# design.net
KiCad netlist of a schematic drawn in Altium Designer
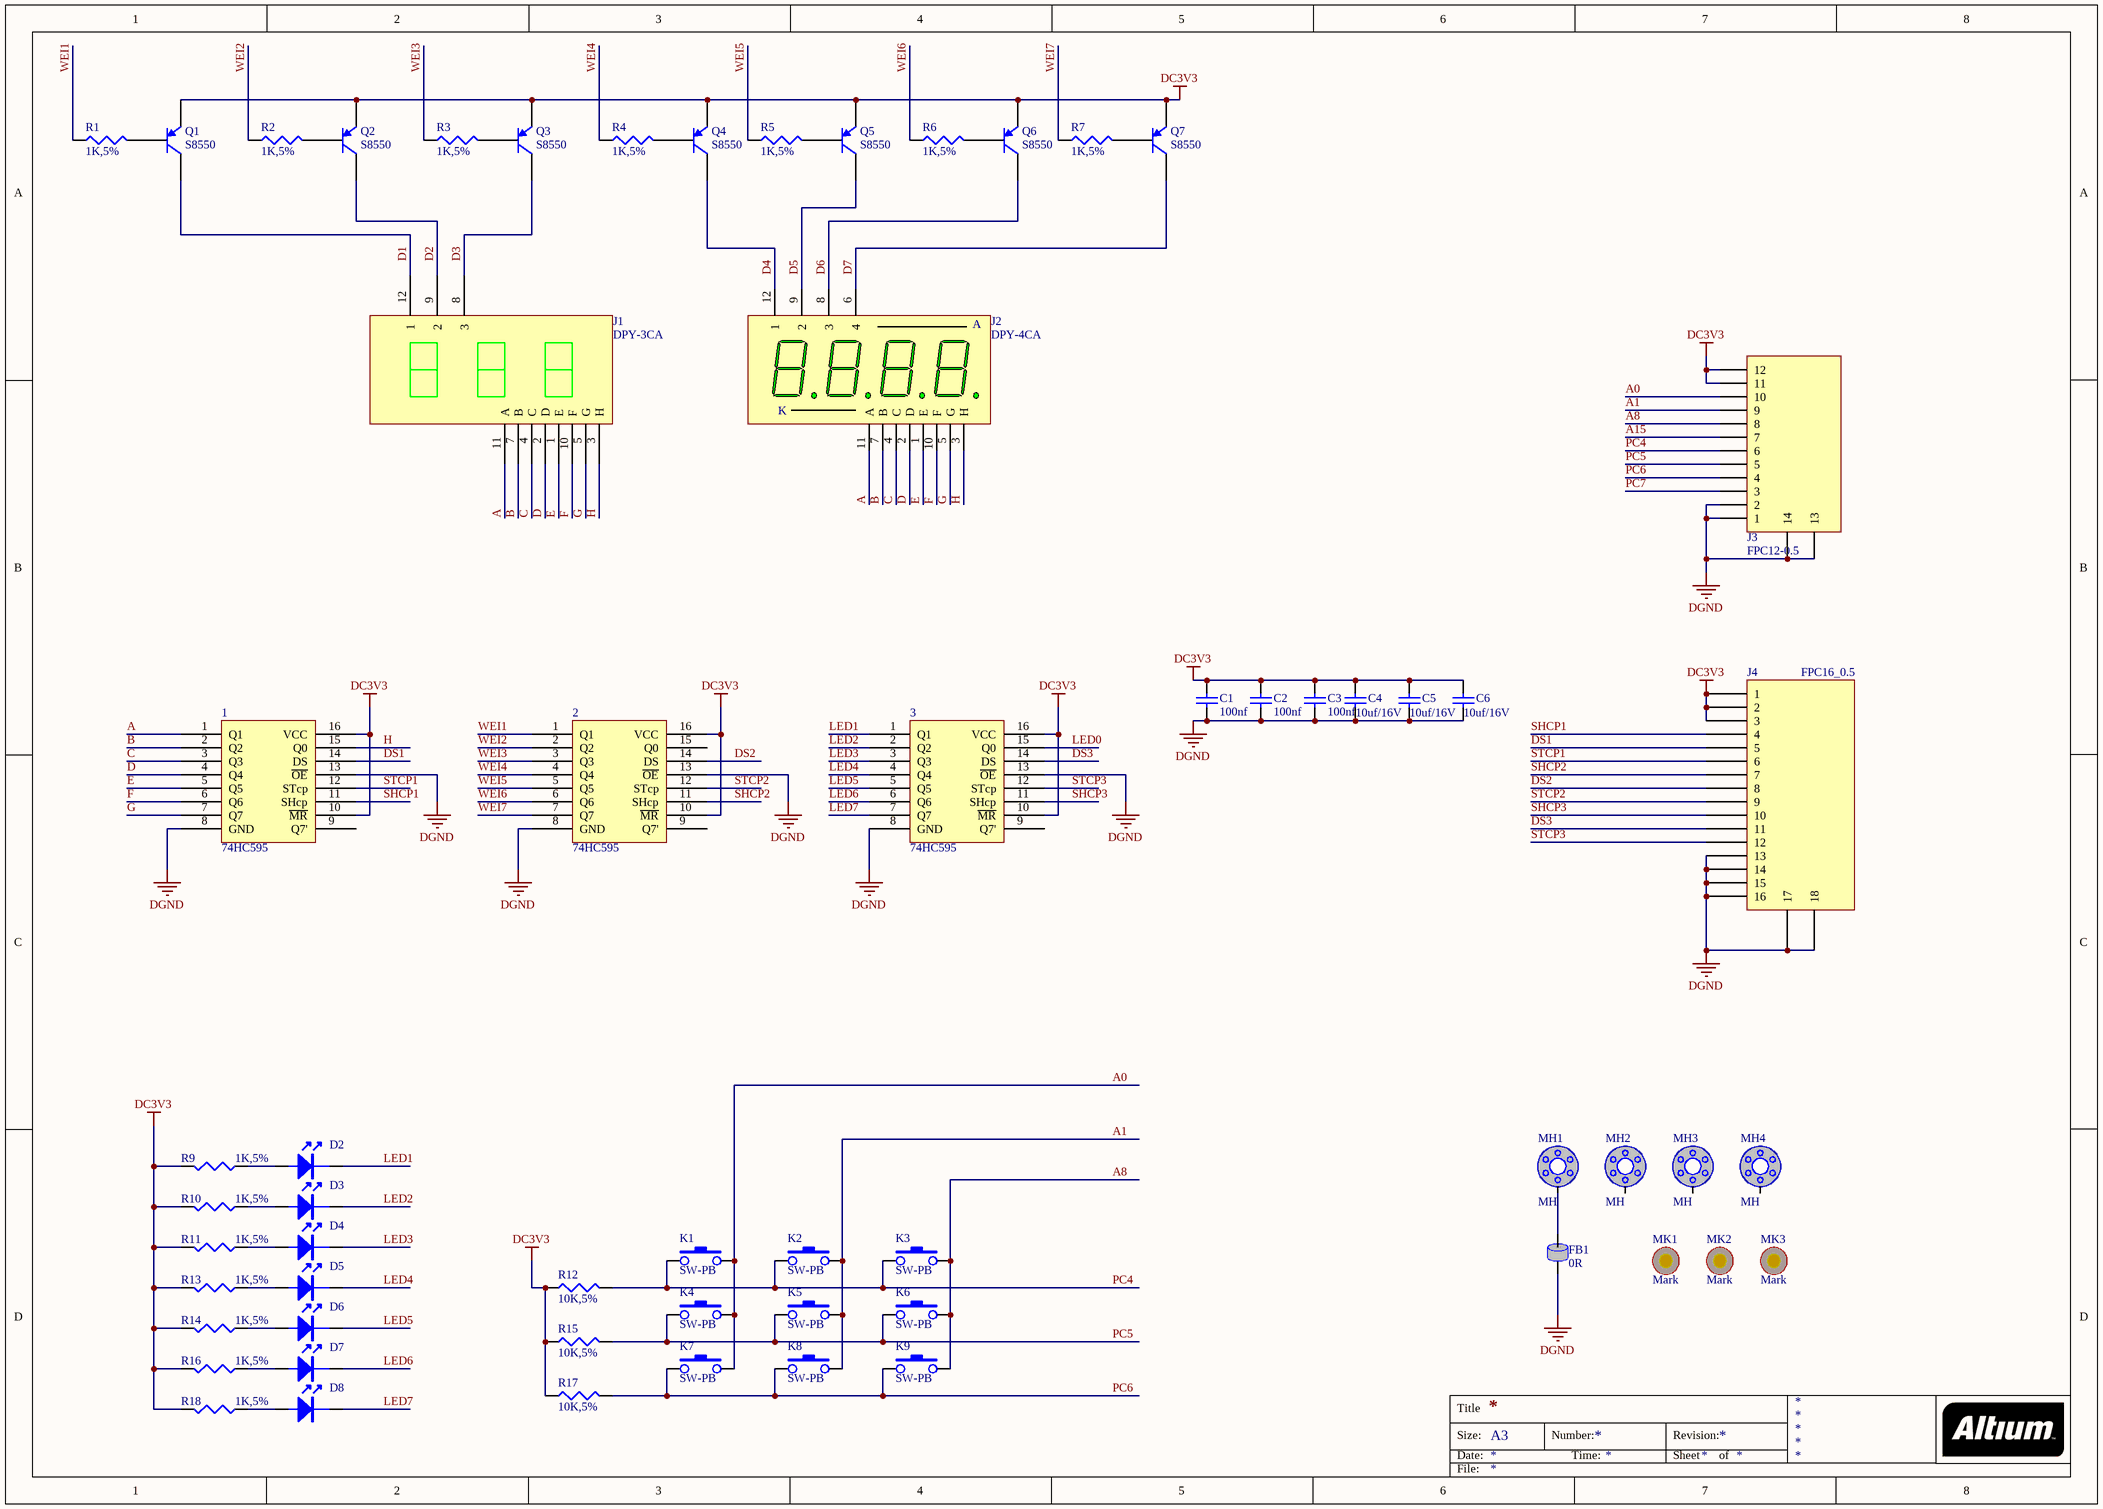
[diagram p0: 显示与输入.SchDoc]

(export (version "E")
  (design (tool "Eeschema 10.0.6"))
  (components
    (comp (ref "1") (value "74HC595") (footprint "SOIC-16") (libsource (lib "74HC595") (part "74HC595")))
    (comp (ref "2") (value "74HC595") (footprint "SOIC-16") (libsource (lib "74HC595") (part "74HC595")))
    (comp (ref "3") (value "74HC595") (footprint "SOIC-16") (libsource (lib "74HC595") (part "74HC595")))
    (comp (ref "C1")
      (value "100nf")
      (footprint "Cap0603")
      (description "无极性电容（表贴）")
      (libsource (lib "MyAD_Library") (part "Cap Semi"))
    )
    (comp (ref "C2")
      (value "100nf")
      (footprint "Cap0603")
      (description "无极性电容（表贴）")
      (libsource (lib "MyAD_Library") (part "Cap Semi"))
    )
    (comp (ref "C3")
      (value "100nf")
      (footprint "Cap0603")
      (description "无极性电容（表贴）")
      (libsource (lib "MyAD_Library") (part "Cap Semi"))
    )
    (comp (ref "C4")
      (value "10uf/16V")
      (footprint "Cap0603")
      (description "无极性电容（表贴）")
      (libsource (lib "MyAD_Library") (part "Cap Semi"))
    )
    (comp (ref "C5")
      (value "10uf/16V")
      (footprint "Cap0603")
      (description "无极性电容（表贴）")
      (libsource (lib "MyAD_Library") (part "Cap Semi"))
    )
    (comp (ref "C6")
      (value "10uf/16V")
      (footprint "Cap0603")
      (description "无极性电容（表贴）")
      (libsource (lib "MyAD_Library") (part "Cap Semi"))
    )
    (comp (ref "D2") (value "LED") (footprint "LED0603") (libsource (lib "MISCESCH") (part "LED")))
    (comp (ref "D3") (value "LED") (footprint "LED0603") (libsource (lib "MISCESCH") (part "LED")))
    (comp (ref "D4") (value "LED") (footprint "LED0603") (libsource (lib "MISCESCH") (part "LED")))
    (comp (ref "D5") (value "LED") (footprint "LED0603") (libsource (lib "MISCESCH") (part "LED")))
    (comp (ref "D6") (value "LED") (footprint "LED0603") (libsource (lib "MISCESCH") (part "LED")))
    (comp (ref "D7") (value "LED") (footprint "LED0603") (libsource (lib "MISCESCH") (part "LED")))
    (comp (ref "D8") (value "LED") (footprint "LED0603") (libsource (lib "MISCESCH") (part "LED")))
    (comp (ref "FB1")
      (value "0R")
      (footprint "FB0603")
      (description "磁珠")
      (libsource (lib "MyAD_Library") (part "FerriteBead"))
    )
    (comp (ref "J1")
      (value "DPY-3CA")
      (footprint "3位数码管0.56寸")
      (description "共阳3位数码管")
      (libsource (lib "fszhang") (part "DPY-3CA"))
    )
    (comp (ref "J2")
      (value "DPY-4CA")
      (footprint "4位数码管0.56寸")
      (description "共阳4位数码管")
      (libsource (lib "fszhang") (part "DPY-4CA"))
    )
    (comp (ref "J3")
      (value "FPC12-0.5")
      (footprint "FPC0.5-12P")
      (libsource (lib "MyAD_Library") (part "FPC12-0.5"))
    )
    (comp (ref "J4")
      (value "FPC16_0.5")
      (footprint "FPC0.5-16P")
      (libsource (lib "MyAD_Schlib") (part "FPC16_0.5"))
    )
    (comp (ref "K1") (value "SW-PB") (footprint "PCB-KEY") (libsource (lib "MISCESCH") (part "SW-PB")))
    (comp (ref "K2") (value "SW-PB") (footprint "PCB-KEY") (libsource (lib "MISCESCH") (part "SW-PB")))
    (comp (ref "K3") (value "SW-PB") (footprint "PCB-KEY") (libsource (lib "MISCESCH") (part "SW-PB")))
    (comp (ref "K4") (value "SW-PB") (footprint "PCB-KEY") (libsource (lib "MISCESCH") (part "SW-PB")))
    (comp (ref "K5") (value "SW-PB") (footprint "PCB-KEY") (libsource (lib "MISCESCH") (part "SW-PB")))
    (comp (ref "K6") (value "SW-PB") (footprint "PCB-KEY") (libsource (lib "MISCESCH") (part "SW-PB")))
    (comp (ref "K7") (value "SW-PB") (footprint "PCB-KEY") (libsource (lib "MISCESCH") (part "SW-PB")))
    (comp (ref "K8") (value "SW-PB") (footprint "PCB-KEY") (libsource (lib "MISCESCH") (part "SW-PB")))
    (comp (ref "K9") (value "SW-PB") (footprint "PCB-KEY") (libsource (lib "MISCESCH") (part "SW-PB")))
    (comp (ref "MH1")
      (value "MH")
      (footprint "AS_D3mm-6mm")
      (description "固定孔")
      (libsource (lib "MyAD_Library") (part "MH"))
    )
    (comp (ref "MH2")
      (value "MH")
      (footprint "AS_D3mm-6mm")
      (description "固定孔")
      (libsource (lib "MyAD_Library") (part "MH"))
    )
    (comp (ref "MH3")
      (value "MH")
      (footprint "AS_D3mm-6mm")
      (description "固定孔")
      (libsource (lib "MyAD_Library") (part "MH"))
    )
    (comp (ref "MH4")
      (value "MH")
      (footprint "AS_D3mm-6mm")
      (description "固定孔")
      (libsource (lib "MyAD_Library") (part "MH"))
    )
    (comp (ref "MK1")
      (value "Mark")
      (footprint "MK")
      (description "贴片马克点")
      (libsource (lib "MyAD_Library") (part "Mark"))
    )
    (comp (ref "MK2")
      (value "Mark")
      (footprint "MK")
      (description "贴片马克点")
      (libsource (lib "MyAD_Library") (part "Mark"))
    )
    (comp (ref "MK3")
      (value "Mark")
      (footprint "MK")
      (description "贴片马克点")
      (libsource (lib "MyAD_Library") (part "Mark"))
    )
    (comp (ref "Q1")
      (value "S8550")
      (footprint "SOT-23B")
      (description "PNP")
      (libsource (lib "MyAD_Schlib") (part "S8550"))
    )
    (comp (ref "Q2")
      (value "S8550")
      (footprint "SOT-23B")
      (description "PNP")
      (libsource (lib "MyAD_Schlib") (part "S8550"))
    )
    (comp (ref "Q3")
      (value "S8550")
      (footprint "SOT-23B")
      (description "PNP")
      (libsource (lib "MyAD_Schlib") (part "S8550"))
    )
    (comp (ref "Q4")
      (value "S8550")
      (footprint "SOT-23B")
      (description "PNP")
      (libsource (lib "MyAD_Schlib") (part "S8550"))
    )
    (comp (ref "Q5")
      (value "S8550")
      (footprint "SOT-23B")
      (description "PNP")
      (libsource (lib "MyAD_Schlib") (part "S8550"))
    )
    (comp (ref "Q6")
      (value "S8550")
      (footprint "SOT-23B")
      (description "PNP")
      (libsource (lib "MyAD_Schlib") (part "S8550"))
    )
    (comp (ref "Q7")
      (value "S8550")
      (footprint "SOT-23B")
      (description "PNP")
      (libsource (lib "MyAD_Schlib") (part "S8550"))
    )
    (comp (ref "R1")
      (value "1K,5%")
      (footprint "Res0603")
      (description "电阻")
      (libsource (lib "MyAD_Schlib") (part "Res"))
    )
    (comp (ref "R2")
      (value "1K,5%")
      (footprint "Res0603")
      (description "电阻")
      (libsource (lib "MyAD_Schlib") (part "Res"))
    )
    (comp (ref "R3")
      (value "1K,5%")
      (footprint "Res0603")
      (description "电阻")
      (libsource (lib "MyAD_Schlib") (part "Res"))
    )
    (comp (ref "R4")
      (value "1K,5%")
      (footprint "Res0603")
      (description "电阻")
      (libsource (lib "MyAD_Schlib") (part "Res"))
    )
    (comp (ref "R5")
      (value "1K,5%")
      (footprint "Res0603")
      (description "电阻")
      (libsource (lib "MyAD_Schlib") (part "Res"))
    )
    (comp (ref "R6")
      (value "1K,5%")
      (footprint "Res0603")
      (description "电阻")
      (libsource (lib "MyAD_Schlib") (part "Res"))
    )
    (comp (ref "R7")
      (value "1K,5%")
      (footprint "Res0603")
      (description "电阻")
      (libsource (lib "MyAD_Schlib") (part "Res"))
    )
    (comp (ref "R9")
      (value "1K,5%")
      (footprint "Res0603")
      (description "电阻")
      (libsource (lib "MyAD_Library") (part "Res"))
    )
    (comp (ref "R10")
      (value "1K,5%")
      (footprint "Res0603")
      (description "电阻")
      (libsource (lib "MyAD_Library") (part "Res"))
    )
    (comp (ref "R11")
      (value "1K,5%")
      (footprint "Res0603")
      (description "电阻")
      (libsource (lib "MyAD_Library") (part "Res"))
    )
    (comp (ref "R12")
      (value "10K,5%")
      (footprint "Res0603")
      (description "电阻")
      (libsource (lib "MyAD_Schlib") (part "Res"))
    )
    (comp (ref "R13")
      (value "1K,5%")
      (footprint "Res0603")
      (description "电阻")
      (libsource (lib "MyAD_Library") (part "Res"))
    )
    (comp (ref "R14")
      (value "1K,5%")
      (footprint "Res0603")
      (description "电阻")
      (libsource (lib "MyAD_Library") (part "Res"))
    )
    (comp (ref "R15")
      (value "10K,5%")
      (footprint "Res0603")
      (description "电阻")
      (libsource (lib "MyAD_Schlib") (part "Res"))
    )
    (comp (ref "R16")
      (value "1K,5%")
      (footprint "Res0603")
      (description "电阻")
      (libsource (lib "MyAD_Library") (part "Res"))
    )
    (comp (ref "R17")
      (value "10K,5%")
      (footprint "Res0603")
      (description "电阻")
      (libsource (lib "MyAD_Schlib") (part "Res"))
    )
    (comp (ref "R18")
      (value "1K,5%")
      (footprint "Res0603")
      (description "电阻")
      (libsource (lib "MyAD_Library") (part "Res"))
    )
  )
  (nets
    (net (code "1") (name "/A") (class "Default")
      (node (ref "1") (pin "1") (pinfunction "Q1_1") (pintype "passive"))
      (node (ref "J1") (pin "11") (pinfunction "A_11") (pintype "passive"))
      (node (ref "J2") (pin "11") (pinfunction "A_11") (pintype "passive"))
    )
    (net (code "2") (name "/A0") (class "Default")
      (node (ref "J3") (pin "10") (pinfunction "10_10") (pintype "passive"))
      (node (ref "K1") (pin "2") (pintype "passive"))
      (node (ref "K4") (pin "2") (pintype "passive"))
      (node (ref "K7") (pin "2") (pintype "passive"))
    )
    (net (code "3") (name "/A1") (class "Default")
      (node (ref "J3") (pin "9") (pinfunction "9_9") (pintype "passive"))
      (node (ref "K2") (pin "2") (pintype "passive"))
      (node (ref "K5") (pin "2") (pintype "passive"))
      (node (ref "K8") (pin "2") (pintype "passive"))
    )
    (net (code "4") (name "/A8") (class "Default")
      (node (ref "J3") (pin "8") (pinfunction "8_8") (pintype "passive"))
      (node (ref "K3") (pin "2") (pintype "passive"))
      (node (ref "K6") (pin "2") (pintype "passive"))
      (node (ref "K9") (pin "2") (pintype "passive"))
    )
    (net (code "5") (name "/A15") (class "Default")
      (node (ref "J3") (pin "7") (pinfunction "7_7") (pintype "passive"))
    )
    (net (code "6") (name "/B") (class "Default")
      (node (ref "1") (pin "2") (pinfunction "Q2_2") (pintype "passive"))
      (node (ref "J1") (pin "7") (pinfunction "B_7") (pintype "passive"))
      (node (ref "J2") (pin "7") (pinfunction "B_7") (pintype "passive"))
    )
    (net (code "7") (name "/C") (class "Default")
      (node (ref "1") (pin "3") (pinfunction "Q3_3") (pintype "passive"))
      (node (ref "J1") (pin "4") (pinfunction "C_4") (pintype "passive"))
      (node (ref "J2") (pin "4") (pinfunction "C_4") (pintype "passive"))
    )
    (net (code "8") (name "/D") (class "Default")
      (node (ref "1") (pin "4") (pinfunction "Q4_4") (pintype "passive"))
      (node (ref "J1") (pin "2") (pinfunction "D_2") (pintype "passive"))
      (node (ref "J2") (pin "2") (pinfunction "D_2") (pintype "passive"))
    )
    (net (code "9") (name "/D1") (class "Default")
      (node (ref "J1") (pin "12") (pinfunction "1_12") (pintype "passive"))
      (node (ref "Q1") (pin "2") (pinfunction "E_2") (pintype "passive"))
    )
    (net (code "10") (name "/D2") (class "Default")
      (node (ref "J1") (pin "9") (pinfunction "2_9") (pintype "passive"))
      (node (ref "Q2") (pin "2") (pinfunction "E_2") (pintype "passive"))
    )
    (net (code "11") (name "/D3") (class "Default")
      (node (ref "J1") (pin "8") (pinfunction "3_8") (pintype "passive"))
      (node (ref "Q3") (pin "2") (pinfunction "E_2") (pintype "passive"))
    )
    (net (code "12") (name "/D4") (class "Default")
      (node (ref "J2") (pin "12") (pinfunction "1_12") (pintype "passive"))
      (node (ref "Q4") (pin "2") (pinfunction "E_2") (pintype "passive"))
    )
    (net (code "13") (name "/D5") (class "Default")
      (node (ref "J2") (pin "9") (pinfunction "2_9") (pintype "passive"))
      (node (ref "Q5") (pin "2") (pinfunction "E_2") (pintype "passive"))
    )
    (net (code "14") (name "/D6") (class "Default")
      (node (ref "J2") (pin "8") (pinfunction "3_8") (pintype "passive"))
      (node (ref "Q6") (pin "2") (pinfunction "E_2") (pintype "passive"))
    )
    (net (code "15") (name "/D7") (class "Default")
      (node (ref "J2") (pin "6") (pinfunction "4_6") (pintype "passive"))
      (node (ref "Q7") (pin "2") (pinfunction "E_2") (pintype "passive"))
    )
    (net (code "16") (name "/DS1") (class "Default")
      (node (ref "1") (pin "14") (pinfunction "DS_14") (pintype "passive"))
      (node (ref "J4") (pin "5") (pinfunction "5_5") (pintype "passive"))
    )
    (net (code "17") (name "/DS2") (class "Default")
      (node (ref "2") (pin "14") (pinfunction "DS_14") (pintype "passive"))
      (node (ref "J4") (pin "8") (pinfunction "8_8") (pintype "passive"))
    )
    (net (code "18") (name "/DS3") (class "Default")
      (node (ref "3") (pin "14") (pinfunction "DS_14") (pintype "passive"))
      (node (ref "J4") (pin "11") (pinfunction "11_11") (pintype "passive"))
    )
    (net (code "19") (name "/E") (class "Default")
      (node (ref "1") (pin "5") (pinfunction "Q5_5") (pintype "passive"))
      (node (ref "J1") (pin "1") (pinfunction "E_1") (pintype "passive"))
      (node (ref "J2") (pin "1") (pinfunction "E_1") (pintype "passive"))
    )
    (net (code "20") (name "/F") (class "Default")
      (node (ref "1") (pin "6") (pinfunction "Q6_6") (pintype "passive"))
      (node (ref "J1") (pin "10") (pinfunction "F_10") (pintype "passive"))
      (node (ref "J2") (pin "10") (pinfunction "F_10") (pintype "passive"))
    )
    (net (code "21") (name "/G") (class "Default")
      (node (ref "1") (pin "7") (pinfunction "Q7_7") (pintype "passive"))
      (node (ref "J1") (pin "5") (pinfunction "G_5") (pintype "passive"))
      (node (ref "J2") (pin "5") (pinfunction "G_5") (pintype "passive"))
    )
    (net (code "22") (name "/H") (class "Default")
      (node (ref "1") (pin "15") (pinfunction "Q0_15") (pintype "passive"))
      (node (ref "J1") (pin "3") (pinfunction "H_3") (pintype "passive"))
      (node (ref "J2") (pin "3") (pinfunction "H_3") (pintype "passive"))
    )
    (net (code "23") (name "/LED0") (class "Default")
      (node (ref "3") (pin "15") (pinfunction "Q0_15") (pintype "passive"))
    )
    (net (code "24") (name "/LED1") (class "Default")
      (node (ref "3") (pin "1") (pinfunction "Q1_1") (pintype "passive"))
      (node (ref "D2") (pin "K") (pinfunction "2_K") (pintype "passive"))
    )
    (net (code "25") (name "/LED2") (class "Default")
      (node (ref "3") (pin "2") (pinfunction "Q2_2") (pintype "passive"))
      (node (ref "D3") (pin "K") (pinfunction "2_K") (pintype "passive"))
    )
    (net (code "26") (name "/LED3") (class "Default")
      (node (ref "3") (pin "3") (pinfunction "Q3_3") (pintype "passive"))
      (node (ref "D4") (pin "K") (pinfunction "2_K") (pintype "passive"))
    )
    (net (code "27") (name "/LED4") (class "Default")
      (node (ref "3") (pin "4") (pinfunction "Q4_4") (pintype "passive"))
      (node (ref "D5") (pin "K") (pinfunction "2_K") (pintype "passive"))
    )
    (net (code "28") (name "/LED5") (class "Default")
      (node (ref "3") (pin "5") (pinfunction "Q5_5") (pintype "passive"))
      (node (ref "D6") (pin "K") (pinfunction "2_K") (pintype "passive"))
    )
    (net (code "29") (name "/LED6") (class "Default")
      (node (ref "3") (pin "6") (pinfunction "Q6_6") (pintype "passive"))
      (node (ref "D7") (pin "K") (pinfunction "2_K") (pintype "passive"))
    )
    (net (code "30") (name "/LED7") (class "Default")
      (node (ref "3") (pin "7") (pinfunction "Q7_7") (pintype "passive"))
      (node (ref "D8") (pin "K") (pinfunction "2_K") (pintype "passive"))
    )
    (net (code "31") (name "/PC4") (class "Default")
      (node (ref "J3") (pin "6") (pinfunction "6_6") (pintype "passive"))
      (node (ref "K1") (pin "1") (pintype "passive"))
      (node (ref "K2") (pin "1") (pintype "passive"))
      (node (ref "K3") (pin "1") (pintype "passive"))
      (node (ref "R12") (pin "2") (pinfunction "2_2") (pintype "passive"))
    )
    (net (code "32") (name "/PC5") (class "Default")
      (node (ref "J3") (pin "5") (pinfunction "5_5") (pintype "passive"))
      (node (ref "K4") (pin "1") (pintype "passive"))
      (node (ref "K5") (pin "1") (pintype "passive"))
      (node (ref "K6") (pin "1") (pintype "passive"))
      (node (ref "R15") (pin "2") (pinfunction "2_2") (pintype "passive"))
    )
    (net (code "33") (name "/PC6") (class "Default")
      (node (ref "J3") (pin "4") (pinfunction "4_4") (pintype "passive"))
      (node (ref "K7") (pin "1") (pintype "passive"))
      (node (ref "K8") (pin "1") (pintype "passive"))
      (node (ref "K9") (pin "1") (pintype "passive"))
      (node (ref "R17") (pin "2") (pinfunction "2_2") (pintype "passive"))
    )
    (net (code "34") (name "/PC7") (class "Default")
      (node (ref "J3") (pin "3") (pinfunction "3_3") (pintype "passive"))
    )
    (net (code "35") (name "/SHCP1") (class "Default")
      (node (ref "1") (pin "11") (pinfunction "SHcp_11") (pintype "passive"))
      (node (ref "J4") (pin "4") (pinfunction "4_4") (pintype "passive"))
    )
    (net (code "36") (name "/SHCP2") (class "Default")
      (node (ref "2") (pin "11") (pinfunction "SHcp_11") (pintype "passive"))
      (node (ref "J4") (pin "7") (pinfunction "7_7") (pintype "passive"))
    )
    (net (code "37") (name "/SHCP3") (class "Default")
      (node (ref "3") (pin "11") (pinfunction "SHcp_11") (pintype "passive"))
      (node (ref "J4") (pin "10") (pinfunction "10_10") (pintype "passive"))
    )
    (net (code "38") (name "/STCP1") (class "Default")
      (node (ref "1") (pin "12") (pinfunction "STcp_12") (pintype "passive"))
      (node (ref "J4") (pin "6") (pinfunction "6_6") (pintype "passive"))
    )
    (net (code "39") (name "/STCP2") (class "Default")
      (node (ref "2") (pin "12") (pinfunction "STcp_12") (pintype "passive"))
      (node (ref "J4") (pin "9") (pinfunction "9_9") (pintype "passive"))
    )
    (net (code "40") (name "/STCP3") (class "Default")
      (node (ref "3") (pin "12") (pinfunction "STcp_12") (pintype "passive"))
      (node (ref "J4") (pin "12") (pinfunction "12_12") (pintype "passive"))
    )
    (net (code "41") (name "/WEI1") (class "Default")
      (node (ref "2") (pin "1") (pinfunction "Q1_1") (pintype "passive"))
      (node (ref "R1") (pin "1") (pinfunction "1_1") (pintype "passive"))
    )
    (net (code "42") (name "/WEI2") (class "Default")
      (node (ref "2") (pin "2") (pinfunction "Q2_2") (pintype "passive"))
      (node (ref "R2") (pin "1") (pinfunction "1_1") (pintype "passive"))
    )
    (net (code "43") (name "/WEI3") (class "Default")
      (node (ref "2") (pin "3") (pinfunction "Q3_3") (pintype "passive"))
      (node (ref "R3") (pin "1") (pinfunction "1_1") (pintype "passive"))
    )
    (net (code "44") (name "/WEI4") (class "Default")
      (node (ref "2") (pin "4") (pinfunction "Q4_4") (pintype "passive"))
      (node (ref "R4") (pin "1") (pinfunction "1_1") (pintype "passive"))
    )
    (net (code "45") (name "/WEI5") (class "Default")
      (node (ref "2") (pin "5") (pinfunction "Q5_5") (pintype "passive"))
      (node (ref "R5") (pin "1") (pinfunction "1_1") (pintype "passive"))
    )
    (net (code "46") (name "/WEI6") (class "Default")
      (node (ref "2") (pin "6") (pinfunction "Q6_6") (pintype "passive"))
      (node (ref "R6") (pin "1") (pinfunction "1_1") (pintype "passive"))
    )
    (net (code "47") (name "/WEI7") (class "Default")
      (node (ref "2") (pin "7") (pinfunction "Q7_7") (pintype "passive"))
      (node (ref "R7") (pin "1") (pinfunction "1_1") (pintype "passive"))
    )
    (net (code "48") (name "DC3V3") (class "Default")
      (node (ref "1") (pin "10") (pinfunction "~{MR}_10") (pintype "passive"))
      (node (ref "1") (pin "16") (pinfunction "VCC_16") (pintype "passive"))
      (node (ref "2") (pin "10") (pinfunction "~{MR}_10") (pintype "passive"))
      (node (ref "2") (pin "16") (pinfunction "VCC_16") (pintype "passive"))
      (node (ref "3") (pin "10") (pinfunction "~{MR}_10") (pintype "passive"))
      (node (ref "3") (pin "16") (pinfunction "VCC_16") (pintype "passive"))
      (node (ref "C1") (pin "2") (pinfunction "2_2") (pintype "passive"))
      (node (ref "C2") (pin "2") (pinfunction "2_2") (pintype "passive"))
      (node (ref "C3") (pin "2") (pinfunction "2_2") (pintype "passive"))
      (node (ref "C4") (pin "2") (pinfunction "2_2") (pintype "passive"))
      (node (ref "C5") (pin "2") (pinfunction "2_2") (pintype "passive"))
      (node (ref "C6") (pin "2") (pinfunction "2_2") (pintype "passive"))
      (node (ref "J3") (pin "11") (pinfunction "11_11") (pintype "passive"))
      (node (ref "J3") (pin "12") (pinfunction "12_12") (pintype "passive"))
      (node (ref "J4") (pin "1") (pinfunction "1_1") (pintype "passive"))
      (node (ref "J4") (pin "2") (pinfunction "2_2") (pintype "passive"))
      (node (ref "J4") (pin "3") (pinfunction "3_3") (pintype "passive"))
      (node (ref "Q1") (pin "3") (pinfunction "C_3") (pintype "passive"))
      (node (ref "Q2") (pin "3") (pinfunction "C_3") (pintype "passive"))
      (node (ref "Q3") (pin "3") (pinfunction "C_3") (pintype "passive"))
      (node (ref "Q4") (pin "3") (pinfunction "C_3") (pintype "passive"))
      (node (ref "Q5") (pin "3") (pinfunction "C_3") (pintype "passive"))
      (node (ref "Q6") (pin "3") (pinfunction "C_3") (pintype "passive"))
      (node (ref "Q7") (pin "3") (pinfunction "C_3") (pintype "passive"))
      (node (ref "R10") (pin "1") (pinfunction "1_1") (pintype "passive"))
      (node (ref "R11") (pin "1") (pinfunction "1_1") (pintype "passive"))
      (node (ref "R12") (pin "1") (pinfunction "1_1") (pintype "passive"))
      (node (ref "R13") (pin "1") (pinfunction "1_1") (pintype "passive"))
      (node (ref "R14") (pin "1") (pinfunction "1_1") (pintype "passive"))
      (node (ref "R15") (pin "1") (pinfunction "1_1") (pintype "passive"))
      (node (ref "R16") (pin "1") (pinfunction "1_1") (pintype "passive"))
      (node (ref "R17") (pin "1") (pinfunction "1_1") (pintype "passive"))
      (node (ref "R18") (pin "1") (pinfunction "1_1") (pintype "passive"))
      (node (ref "R9") (pin "1") (pinfunction "1_1") (pintype "passive"))
    )
    (net (code "49") (name "DGND") (class "Default")
      (node (ref "1") (pin "13") (pinfunction "~{OE}_13") (pintype "passive"))
      (node (ref "1") (pin "8") (pinfunction "GND_8") (pintype "passive"))
      (node (ref "2") (pin "13") (pinfunction "~{OE}_13") (pintype "passive"))
      (node (ref "2") (pin "8") (pinfunction "GND_8") (pintype "passive"))
      (node (ref "3") (pin "13") (pinfunction "~{OE}_13") (pintype "passive"))
      (node (ref "3") (pin "8") (pinfunction "GND_8") (pintype "passive"))
      (node (ref "C1") (pin "1") (pinfunction "1_1") (pintype "passive"))
      (node (ref "C2") (pin "1") (pinfunction "1_1") (pintype "passive"))
      (node (ref "C3") (pin "1") (pinfunction "1_1") (pintype "passive"))
      (node (ref "C4") (pin "1") (pinfunction "1_1") (pintype "passive"))
      (node (ref "C5") (pin "1") (pinfunction "1_1") (pintype "passive"))
      (node (ref "C6") (pin "1") (pinfunction "1_1") (pintype "passive"))
      (node (ref "FB1") (pin "1") (pinfunction "1_1") (pintype "passive"))
      (node (ref "J3") (pin "1") (pinfunction "1_1") (pintype "passive"))
      (node (ref "J3") (pin "13") (pinfunction "13_13") (pintype "passive"))
      (node (ref "J3") (pin "14") (pinfunction "14_14") (pintype "passive"))
      (node (ref "J3") (pin "2") (pinfunction "2_2") (pintype "passive"))
      (node (ref "J4") (pin "13") (pinfunction "13_13") (pintype "passive"))
      (node (ref "J4") (pin "14") (pinfunction "14_14") (pintype "passive"))
      (node (ref "J4") (pin "15") (pinfunction "15_15") (pintype "passive"))
      (node (ref "J4") (pin "16") (pinfunction "16_16") (pintype "passive"))
      (node (ref "J4") (pin "17") (pinfunction "17_17") (pintype "passive"))
      (node (ref "J4") (pin "18") (pinfunction "18_18") (pintype "passive"))
    )
    (net (code "50") (name "Net-(D2-1)") (class "Default")
      (node (ref "D2") (pin "A") (pinfunction "1_A") (pintype "passive"))
      (node (ref "R9") (pin "2") (pinfunction "2_2") (pintype "passive"))
    )
    (net (code "51") (name "Net-(D3-1)") (class "Default")
      (node (ref "D3") (pin "A") (pinfunction "1_A") (pintype "passive"))
      (node (ref "R10") (pin "2") (pinfunction "2_2") (pintype "passive"))
    )
    (net (code "52") (name "Net-(D4-1)") (class "Default")
      (node (ref "D4") (pin "A") (pinfunction "1_A") (pintype "passive"))
      (node (ref "R11") (pin "2") (pinfunction "2_2") (pintype "passive"))
    )
    (net (code "53") (name "Net-(D5-1)") (class "Default")
      (node (ref "D5") (pin "A") (pinfunction "1_A") (pintype "passive"))
      (node (ref "R13") (pin "2") (pinfunction "2_2") (pintype "passive"))
    )
    (net (code "54") (name "Net-(D6-1)") (class "Default")
      (node (ref "D6") (pin "A") (pinfunction "1_A") (pintype "passive"))
      (node (ref "R14") (pin "2") (pinfunction "2_2") (pintype "passive"))
    )
    (net (code "55") (name "Net-(D7-1)") (class "Default")
      (node (ref "D7") (pin "A") (pinfunction "1_A") (pintype "passive"))
      (node (ref "R16") (pin "2") (pinfunction "2_2") (pintype "passive"))
    )
    (net (code "56") (name "Net-(D8-1)") (class "Default")
      (node (ref "D8") (pin "A") (pinfunction "1_A") (pintype "passive"))
      (node (ref "R18") (pin "2") (pinfunction "2_2") (pintype "passive"))
    )
    (net (code "57") (name "Net-(FB1-Pad2)") (class "Default")
      (node (ref "FB1") (pin "2") (pinfunction "2_2") (pintype "passive"))
      (node (ref "MH1") (pin "MH1") (pinfunction "MH1_MH1") (pintype "passive"))
    )
    (net (code "58") (name "Net-(Q1-B)") (class "Default")
      (node (ref "Q1") (pin "1") (pinfunction "B_1") (pintype "passive"))
      (node (ref "R1") (pin "2") (pinfunction "2_2") (pintype "passive"))
    )
    (net (code "59") (name "Net-(Q2-B)") (class "Default")
      (node (ref "Q2") (pin "1") (pinfunction "B_1") (pintype "passive"))
      (node (ref "R2") (pin "2") (pinfunction "2_2") (pintype "passive"))
    )
    (net (code "60") (name "Net-(Q3-B)") (class "Default")
      (node (ref "Q3") (pin "1") (pinfunction "B_1") (pintype "passive"))
      (node (ref "R3") (pin "2") (pinfunction "2_2") (pintype "passive"))
    )
    (net (code "61") (name "Net-(Q4-B)") (class "Default")
      (node (ref "Q4") (pin "1") (pinfunction "B_1") (pintype "passive"))
      (node (ref "R4") (pin "2") (pinfunction "2_2") (pintype "passive"))
    )
    (net (code "62") (name "Net-(Q5-B)") (class "Default")
      (node (ref "Q5") (pin "1") (pinfunction "B_1") (pintype "passive"))
      (node (ref "R5") (pin "2") (pinfunction "2_2") (pintype "passive"))
    )
    (net (code "63") (name "Net-(Q6-B)") (class "Default")
      (node (ref "Q6") (pin "1") (pinfunction "B_1") (pintype "passive"))
      (node (ref "R6") (pin "2") (pinfunction "2_2") (pintype "passive"))
    )
    (net (code "64") (name "Net-(Q7-B)") (class "Default")
      (node (ref "Q7") (pin "1") (pinfunction "B_1") (pintype "passive"))
      (node (ref "R7") (pin "2") (pinfunction "2_2") (pintype "passive"))
    )
    (net (code "65") (name "unconnected-(1-Q7'-Pad9)") (class "Default")
      (node (ref "1") (pin "9") (pinfunction "Q7'_9") (pintype "passive"))
    )
    (net (code "66") (name "unconnected-(2-Q0-Pad15)") (class "Default")
      (node (ref "2") (pin "15") (pinfunction "Q0_15") (pintype "passive"))
    )
    (net (code "67") (name "unconnected-(2-Q7'-Pad9)") (class "Default")
      (node (ref "2") (pin "9") (pinfunction "Q7'_9") (pintype "passive"))
    )
    (net (code "68") (name "unconnected-(3-Q7'-Pad9)") (class "Default")
      (node (ref "3") (pin "9") (pinfunction "Q7'_9") (pintype "passive"))
    )
    (net (code "69") (name "unconnected-(MH2-PadMH1)") (class "Default")
      (node (ref "MH2") (pin "MH1") (pinfunction "MH1_MH1") (pintype "passive"))
    )
    (net (code "70") (name "unconnected-(MH3-PadMH1)") (class "Default")
      (node (ref "MH3") (pin "MH1") (pinfunction "MH1_MH1") (pintype "passive"))
    )
    (net (code "71") (name "unconnected-(MH4-PadMH1)") (class "Default")
      (node (ref "MH4") (pin "MH1") (pinfunction "MH1_MH1") (pintype "passive"))
    )
  )
)
